# Si4455.net
KiCad netlist of a schematic drawn in Altium Designer
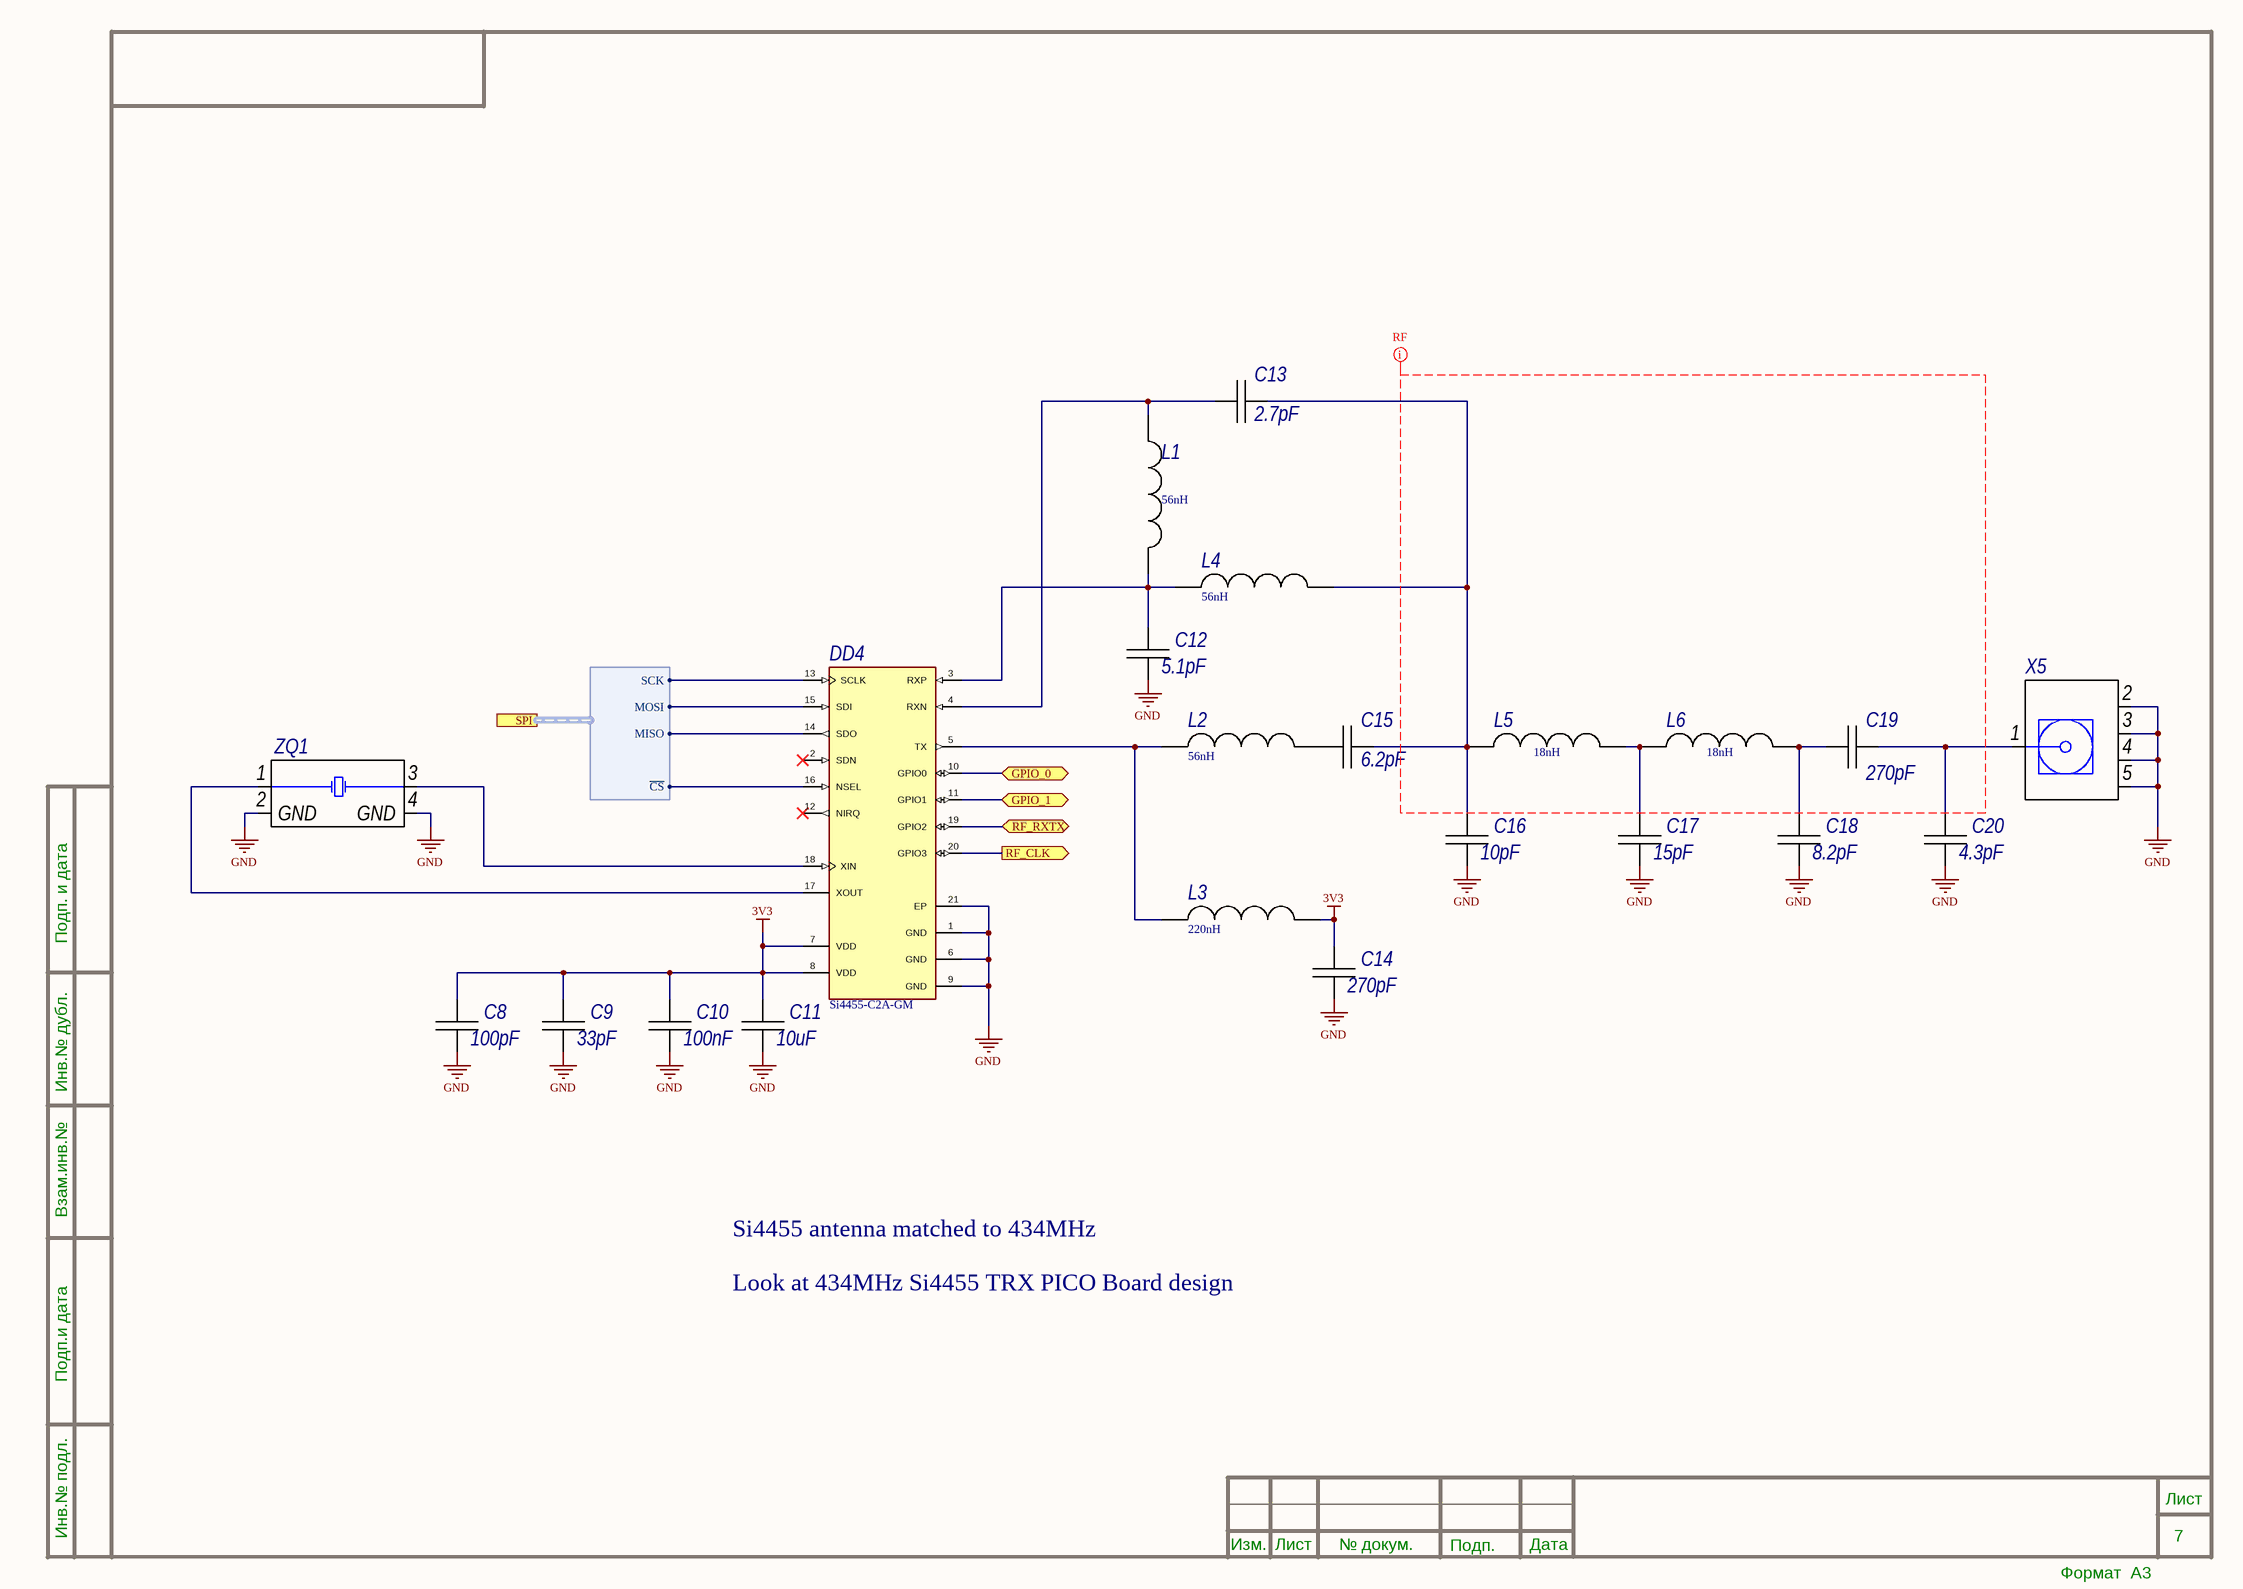
[diagram p0: Si4455.SchDoc]

(export (version "E")
  (design (tool "Eeschema 10.0.6"))
  (components
    (comp (ref "C8")
      (value "100pF")
      (footprint "CAP0402")
      (fields (field (name "PART NUMBER") "CAP0402") (field (name "Comment") "100pF "))
      (libsource (lib "Library") (part "CAPC"))
    )
    (comp (ref "C9")
      (value "33pF")
      (footprint "CAP0402")
      (fields (field (name "PART NUMBER") "CAP0402") (field (name "Comment") "33pF "))
      (libsource (lib "Library") (part "CAPC"))
    )
    (comp (ref "C10")
      (value "100nF")
      (footprint "CAP0402")
      (fields (field (name "PART NUMBER") "CAP0402") (field (name "Comment") "100nF "))
      (libsource (lib "Library") (part "CAPC"))
    )
    (comp (ref "C11")
      (value "10uF")
      (footprint "CAPC0603N")
      (fields (field (name "PART NUMBER") "CAPC") (field (name "Comment") "10uF "))
      (libsource (lib "Library") (part "CAPC"))
    )
    (comp (ref "C12")
      (value "5.1pF")
      (footprint "CAP0402")
      (fields (field (name "PART NUMBER") "CAP0402") (field (name "Comment") "5.1pF "))
      (libsource (lib "Library") (part "CAPC"))
    )
    (comp (ref "C13")
      (value "2.7pF")
      (footprint "CAP0402")
      (fields (field (name "PART NUMBER") "CAP0402") (field (name "Comment") "2.7pF "))
      (libsource (lib "Library") (part "CAPC"))
    )
    (comp (ref "C14")
      (value "270pF")
      (footprint "CAP0402")
      (fields (field (name "PART NUMBER") "CAP0402") (field (name "Comment") "270pF "))
      (libsource (lib "Library") (part "CAPC"))
    )
    (comp (ref "C15")
      (value "6.2pF")
      (footprint "CAP0402")
      (fields (field (name "PART NUMBER") "CAP0402") (field (name "Comment") "6.2pF "))
      (libsource (lib "Library") (part "CAPC"))
    )
    (comp (ref "C16")
      (value "10pF")
      (footprint "CAP0402")
      (fields (field (name "PART NUMBER") "CAP0402") (field (name "Comment") "10pF "))
      (libsource (lib "Library") (part "CAPC"))
    )
    (comp (ref "C17")
      (value "15pF")
      (footprint "CAP0402")
      (fields (field (name "PART NUMBER") "CAP0402") (field (name "Comment") "15pF "))
      (libsource (lib "Library") (part "CAPC"))
    )
    (comp (ref "C18")
      (value "8.2pF")
      (footprint "CAP0402")
      (fields (field (name "PART NUMBER") "CAP0402") (field (name "Comment") "8.2pF "))
      (libsource (lib "Library") (part "CAPC"))
    )
    (comp (ref "C19")
      (value "270pF")
      (footprint "CAP0402")
      (fields (field (name "PART NUMBER") "CAP0402") (field (name "Comment") "270pF "))
      (libsource (lib "Library") (part "CAPC"))
    )
    (comp (ref "C20")
      (value "4.3pF")
      (footprint "CAP0402")
      (fields (field (name "PART NUMBER") "CAP0402") (field (name "Comment") "4.3pF "))
      (libsource (lib "Library") (part "CAPC"))
    )
    (comp (ref "DD4")
      (value "Si4455-С2A-GM")
      (footprint "SLAB-QFN-20")
      (fields (field (name "MANUFACTURER") "SiLabs"))
      (libsource (lib "Library") (part "Si4455-С2A-GM"))
    )
    (comp (ref "L1")
      (value "56nH")
      (footprint "RESC0402(1005)_M")
      (fields
        (field (name "MANUFACTURER") "TDK")
        (field (name "MPN") "MLF2012")
        (field (name "PART NUMBER") "Inductor_SMD")
      )
      (libsource (lib "Library") (part "Inductor"))
    )
    (comp (ref "L2")
      (value "56nH")
      (footprint "RESC0402(1005)_M")
      (fields
        (field (name "MANUFACTURER") "TDK")
        (field (name "MPN") "MLF2012")
        (field (name "PART NUMBER") "Inductor_SMD")
      )
      (libsource (lib "Library") (part "Inductor"))
    )
    (comp (ref "L3")
      (value "220nH")
      (footprint "RESC0402(1005)_M")
      (fields
        (field (name "MANUFACTURER") "TDK")
        (field (name "MPN") "MLF2012")
        (field (name "PART NUMBER") "Inductor_SMD")
      )
      (libsource (lib "Library") (part "Inductor"))
    )
    (comp (ref "L4")
      (value "56nH")
      (footprint "RESC0402(1005)_M")
      (fields
        (field (name "MANUFACTURER") "TDK")
        (field (name "MPN") "MLF2012")
        (field (name "PART NUMBER") "Inductor_SMD")
      )
      (libsource (lib "Library") (part "Inductor"))
    )
    (comp (ref "L5")
      (value "18nH")
      (footprint "RESC0402(1005)_M")
      (fields
        (field (name "MANUFACTURER") "TDK")
        (field (name "MPN") "MLF2012")
        (field (name "PART NUMBER") "Inductor_SMD")
      )
      (libsource (lib "Library") (part "Inductor"))
    )
    (comp (ref "L6")
      (value "18nH")
      (footprint "RESC0402(1005)_M")
      (fields
        (field (name "MANUFACTURER") "TDK")
        (field (name "MPN") "MLF2012")
        (field (name "PART NUMBER") "Inductor_SMD")
      )
      (libsource (lib "Library") (part "Inductor"))
    )
    (comp (ref "X5")
      (value "~")
      (footprint "60311042114502")
      (fields
        (field (name "PART NUMBER") "SMA_WR_60311042114502")
        (field (name "MANUFACTURER") "WE")
        (field (name "MPN") "60311042114502")
      )
      (libsource (lib "Library") (part "SMA_WR_60311042114502"))
    )
    (comp (ref "ZQ1")
      (value "X322525MOB4SI")
      (footprint "TSX-3225_V")
      (fields (field (name "MANUFACTURER") "Yangxing Tech"))
      (libsource (lib "Library") (part "Crystal_TSX-3225_24M"))
    )
  )
  (nets
    (net (code "2") (name "/GPIO_0") (class "Default")
      (node (ref "DD4") (pin "10") (pinfunction "GPIO0_10") (pintype "bidirectional"))
    )
    (net (code "3") (name "/GPIO_1") (class "Default")
      (node (ref "DD4") (pin "11") (pinfunction "GPIO1_11") (pintype "bidirectional"))
    )
    (net (code "4") (name "/MISO") (class "Default")
      (node (ref "DD4") (pin "14") (pinfunction "SDO_14") (pintype "output"))
    )
    (net (code "5") (name "/MOSI") (class "Default")
      (node (ref "DD4") (pin "15") (pinfunction "SDI_15") (pintype "input"))
    )
    (net (code "6") (name "/RF_CLK") (class "Default")
      (node (ref "DD4") (pin "20") (pinfunction "GPIO3_20") (pintype "bidirectional"))
    )
    (net (code "7") (name "/RF_RXTX") (class "Default")
      (node (ref "DD4") (pin "19") (pinfunction "GPIO2_19") (pintype "bidirectional"))
    )
    (net (code "8") (name "/SCK") (class "Default")
      (node (ref "DD4") (pin "13") (pinfunction "SCLK_13") (pintype "input"))
    )
    (net (code "10") (name "/~{CS}") (class "Default")
      (node (ref "DD4") (pin "16") (pinfunction "NSEL_16") (pintype "input"))
    )
    (net (code "11") (name "3V3") (class "Default")
      (node (ref "C10") (pin "2") (pinfunction "2_2") (pintype "passive"))
      (node (ref "C11") (pin "1") (pinfunction "1_1") (pintype "passive"))
      (node (ref "C14") (pin "1") (pinfunction "1_1") (pintype "passive"))
      (node (ref "C8") (pin "2") (pinfunction "2_2") (pintype "passive"))
      (node (ref "C9") (pin "2") (pinfunction "2_2") (pintype "passive"))
      (node (ref "DD4") (pin "7") (pinfunction "VDD_7") (pintype "power_in"))
      (node (ref "DD4") (pin "8") (pinfunction "VDD_8") (pintype "power_in"))
      (node (ref "L3") (pin "2") (pinfunction "2_2") (pintype "passive"))
    )
    (net (code "12") (name "GND") (class "Default")
      (node (ref "C10") (pin "1") (pinfunction "1_1") (pintype "passive"))
      (node (ref "C11") (pin "2") (pinfunction "2_2") (pintype "passive"))
      (node (ref "C12") (pin "2") (pinfunction "2_2") (pintype "passive"))
      (node (ref "C14") (pin "2") (pinfunction "2_2") (pintype "passive"))
      (node (ref "C16") (pin "2") (pinfunction "2_2") (pintype "passive"))
      (node (ref "C17") (pin "2") (pinfunction "2_2") (pintype "passive"))
      (node (ref "C18") (pin "2") (pinfunction "2_2") (pintype "passive"))
      (node (ref "C20") (pin "2") (pinfunction "2_2") (pintype "passive"))
      (node (ref "C8") (pin "1") (pinfunction "1_1") (pintype "passive"))
      (node (ref "C9") (pin "1") (pinfunction "1_1") (pintype "passive"))
      (node (ref "DD4") (pin "1") (pinfunction "GND_1") (pintype "power_in"))
      (node (ref "DD4") (pin "21") (pinfunction "EP_21") (pintype "passive"))
      (node (ref "DD4") (pin "6") (pinfunction "GND_6") (pintype "power_in"))
      (node (ref "DD4") (pin "9") (pinfunction "GND_9") (pintype "power_in"))
      (node (ref "X5") (pin "2") (pinfunction "GND_2") (pintype "power_in"))
      (node (ref "X5") (pin "3") (pinfunction "GND_3") (pintype "power_in"))
      (node (ref "X5") (pin "4") (pinfunction "GND_4") (pintype "power_in"))
      (node (ref "X5") (pin "5") (pinfunction "GND_5") (pintype "power_in"))
      (node (ref "ZQ1") (pin "2") (pinfunction "GND_2") (pintype "power_in"))
      (node (ref "ZQ1") (pin "4") (pinfunction "GND_4") (pintype "power_in"))
    )
    (net (code "13") (name "Net-(C13-Pad1)") (class "Default")
      (node (ref "C13") (pin "1") (pinfunction "1_1") (pintype "passive"))
      (node (ref "C15") (pin "1") (pinfunction "1_1") (pintype "passive"))
      (node (ref "C16") (pin "1") (pinfunction "1_1") (pintype "passive"))
      (node (ref "L4") (pin "2") (pinfunction "2_2") (pintype "passive"))
      (node (ref "L5") (pin "1") (pinfunction "1_1") (pintype "passive"))
    )
    (net (code "14") (name "Net-(C15-Pad2)") (class "Default")
      (node (ref "C15") (pin "2") (pinfunction "2_2") (pintype "passive"))
      (node (ref "L2") (pin "2") (pinfunction "2_2") (pintype "passive"))
    )
    (net (code "15") (name "Net-(C17-Pad1)") (class "Default")
      (node (ref "C17") (pin "1") (pinfunction "1_1") (pintype "passive"))
      (node (ref "L5") (pin "2") (pinfunction "2_2") (pintype "passive"))
      (node (ref "L6") (pin "1") (pinfunction "1_1") (pintype "passive"))
    )
    (net (code "16") (name "Net-(C18-Pad1)") (class "Default")
      (node (ref "C18") (pin "1") (pinfunction "1_1") (pintype "passive"))
      (node (ref "C19") (pin "1") (pinfunction "1_1") (pintype "passive"))
      (node (ref "L6") (pin "2") (pinfunction "2_2") (pintype "passive"))
    )
    (net (code "17") (name "Net-(DD4-RXN)") (class "Default")
      (node (ref "C13") (pin "2") (pinfunction "2_2") (pintype "passive"))
      (node (ref "DD4") (pin "4") (pinfunction "RXN_4") (pintype "input"))
      (node (ref "L1") (pin "1") (pinfunction "1_1") (pintype "passive"))
    )
    (net (code "18") (name "Net-(DD4-RXP)") (class "Default")
      (node (ref "C12") (pin "1") (pinfunction "1_1") (pintype "passive"))
      (node (ref "DD4") (pin "3") (pinfunction "RXP_3") (pintype "input"))
      (node (ref "L1") (pin "2") (pinfunction "2_2") (pintype "passive"))
      (node (ref "L4") (pin "1") (pinfunction "1_1") (pintype "passive"))
    )
    (net (code "19") (name "Net-(DD4-TX)") (class "Default")
      (node (ref "DD4") (pin "5") (pinfunction "TX_5") (pintype "output"))
      (node (ref "L2") (pin "1") (pinfunction "1_1") (pintype "passive"))
      (node (ref "L3") (pin "1") (pinfunction "1_1") (pintype "passive"))
    )
    (net (code "20") (name "Net-(DD4-XIN)") (class "Default")
      (node (ref "DD4") (pin "18") (pinfunction "XIN_18") (pintype "input"))
      (node (ref "ZQ1") (pin "3") (pinfunction "X2_3") (pintype "passive"))
    )
    (net (code "21") (name "Net-(DD4-XOUT)") (class "Default")
      (node (ref "DD4") (pin "17") (pinfunction "XOUT_17") (pintype "passive"))
      (node (ref "ZQ1") (pin "1") (pinfunction "X1_1") (pintype "passive"))
    )
    (net (code "22") (name "Net-(X5-Signal)") (class "Default")
      (node (ref "C19") (pin "2") (pinfunction "2_2") (pintype "passive"))
      (node (ref "C20") (pin "1") (pinfunction "1_1") (pintype "passive"))
      (node (ref "X5") (pin "1") (pinfunction "Signal_1") (pintype "passive"))
    )
    (net (code "23") (name "unconnected-(DD4-NIRQ-Pad12)") (class "Default")
      (node (ref "DD4") (pin "12") (pinfunction "NIRQ_12") (pintype "output+no_connect"))
    )
    (net (code "24") (name "unconnected-(DD4-SDN-Pad2)") (class "Default")
      (node (ref "DD4") (pin "2") (pinfunction "SDN_2") (pintype "input+no_connect"))
    )
  )
)
